# Lyra_Main_Solo.net
KiCad netlist of a schematic drawn in EAGLE
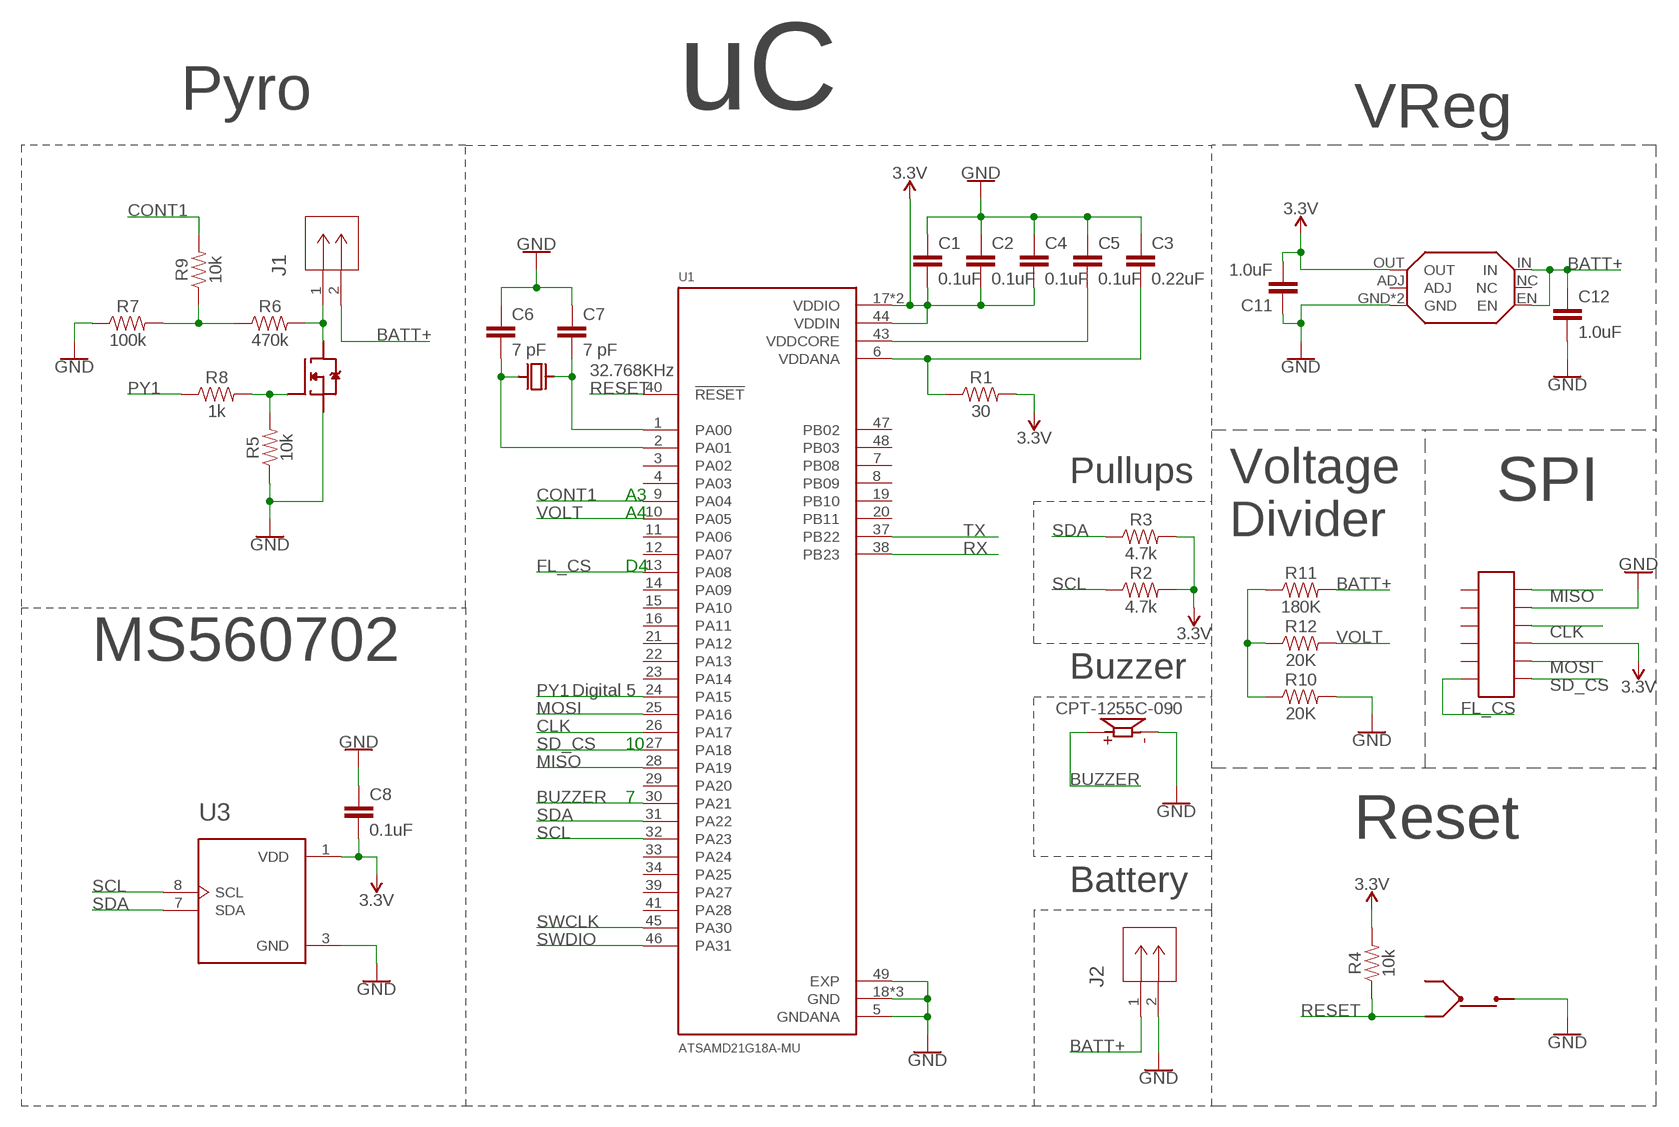
[diagram p0: schematic, sheet 1]

(export (version "E")
  (design (tool "Eeschema 10.0.6"))
  (components
    (comp (ref "C1")
      (value "0.1uF")
      (footprint "eagle-import:0603")
      (libsource (lib "eagle-import") (part "0.1UF-0603-25V-(+80/-20%)"))
    )
    (comp (ref "C2")
      (value "0.1uF")
      (footprint "eagle-import:0603")
      (libsource (lib "eagle-import") (part "0.1UF-0603-25V-(+80/-20%)"))
    )
    (comp (ref "C3")
      (value "0.22uF")
      (footprint "eagle-import:0603")
      (libsource (lib "eagle-import") (part "0.1UF-0603-25V-(+80/-20%)"))
    )
    (comp (ref "C4")
      (value "0.1uF")
      (footprint "eagle-import:0603")
      (libsource (lib "eagle-import") (part "0.1UF-0603-25V-(+80/-20%)"))
    )
    (comp (ref "C5")
      (value "0.1uF")
      (footprint "eagle-import:0603")
      (libsource (lib "eagle-import") (part "0.1UF-0603-25V-(+80/-20%)"))
    )
    (comp (ref "C6")
      (value "7 pF")
      (footprint "eagle-import:0402")
      (libsource (lib "eagle-import") (part "0.1UF-0402-16V-10%"))
    )
    (comp (ref "C7")
      (value "7 pF")
      (footprint "eagle-import:0402")
      (libsource (lib "eagle-import") (part "0.1UF-0402-16V-10%"))
    )
    (comp (ref "C8")
      (value "0.1uF")
      (footprint "eagle-import:0603")
      (libsource (lib "eagle-import") (part "0.1UF-0603-25V-(+80/-20%)"))
    )
    (comp (ref "C11")
      (value "1.0uF")
      (footprint "eagle-import:0402")
      (libsource (lib "eagle-import") (part "1.0UF-0402-16V-10%"))
    )
    (comp (ref "C12")
      (value "1.0uF")
      (footprint "eagle-import:0402")
      (libsource (lib "eagle-import") (part "1.0UF-0402-16V-10%"))
    )
    (comp (ref "J1")
      (value "OSTVN02A150")
      (footprint "eagle-import:CONN_OSTVN02A150_OST")
      (fields (field (name "COPYRIGHT") "Copyright (C) 2018 Accelerated Designs. All rights reserved"))
      (libsource (lib "eagle-import") (part "OSTVN02A150"))
    )
    (comp (ref "J2")
      (value "OSTVN02A150")
      (footprint "eagle-import:CONN_OSTVN02A150_OST")
      (fields (field (name "COPYRIGHT") "Copyright (C) 2018 Accelerated Designs. All rights reserved"))
      (libsource (lib "eagle-import") (part "OSTVN02A150"))
    )
    (comp (ref "LS2")
      (value "CPT-1255C-090")
      (footprint "eagle-import:CUI_CPT-1255C-090")
      (fields (field (name "MF") "CUI Devices"))
      (libsource (lib "eagle-import") (part "CPT-1255C-090"))
    )
    (comp (ref "R1")
      (value "30")
      (footprint "eagle-import:0402")
      (libsource (lib "eagle-import") (part "RESISTOR0402"))
    )
    (comp (ref "R2")
      (value "4.7k")
      (footprint "eagle-import:0603")
      (libsource (lib "eagle-import") (part "4.7KOHM-0603-1/10W-1%"))
    )
    (comp (ref "R3")
      (value "4.7k")
      (footprint "eagle-import:0603")
      (libsource (lib "eagle-import") (part "4.7KOHM-0603-1/10W-1%"))
    )
    (comp (ref "R4")
      (value "10k")
      (footprint "eagle-import:0402")
      (libsource (lib "eagle-import") (part "RESISTOR0402"))
    )
    (comp (ref "R5")
      (value "10k")
      (footprint "eagle-import:0402")
      (libsource (lib "eagle-import") (part "RESISTOR0402"))
    )
    (comp (ref "R6")
      (value "470k")
      (footprint "eagle-import:0402")
      (libsource (lib "eagle-import") (part "RESISTOR0402"))
    )
    (comp (ref "R7")
      (value "100k")
      (footprint "eagle-import:0402")
      (libsource (lib "eagle-import") (part "RESISTOR0402"))
    )
    (comp (ref "R8")
      (value "1k")
      (footprint "eagle-import:0402")
      (libsource (lib "eagle-import") (part "RESISTOR0402"))
    )
    (comp (ref "R9")
      (value "10k")
      (footprint "eagle-import:0402")
      (libsource (lib "eagle-import") (part "RESISTOR0402"))
    )
    (comp (ref "R10")
      (value "20K")
      (footprint "eagle-import:0402")
      (libsource (lib "eagle-import") (part "RESISTOR0402"))
    )
    (comp (ref "R11")
      (value "180K")
      (footprint "eagle-import:0402")
      (libsource (lib "eagle-import") (part "RESISTOR0402"))
    )
    (comp (ref "R12")
      (value "20K")
      (footprint "eagle-import:0402")
      (libsource (lib "eagle-import") (part "RESISTOR0402"))
    )
    (comp (ref "U$1")
      (value "32.768KHz")
      (footprint "eagle-import:FC-135")
      (libsource (lib "eagle-import") (part "FC-135"))
    )
    (comp (ref "U$2")
      (value "IRLHM630PBF")
      (footprint "eagle-import:IRLHM630PBF")
      (libsource (lib "eagle-import") (part "IRLHM630PBF"))
    )
    (comp (ref "U$3")
      (value "NCP718AMT330TBG")
      (footprint "eagle-import:NCP718BMT330TBG")
      (libsource (lib "eagle-import") (part "NCP718AMT330TBG"))
    )
    (comp (ref "U$4")
      (value "BUTTON")
      (footprint "eagle-import:BUTTON")
      (libsource (lib "eagle-import") (part "BUTTON"))
    )
    (comp (ref "U$5")
      (value "12POS_SOCKET")
      (footprint "eagle-import:12POS_SOCKET")
      (libsource (lib "eagle-import") (part "12POS_SOCKET"))
    )
    (comp (ref "U1")
      (value "ATSAMD21G18A-MU")
      (footprint "eagle-import:QFN50P700X700X90-49N")
      (fields (field (name "DIGI-KEY_PART_NUMBER") "ATSAMD21G18A-MUTTR-ND") (field (name "MF") "Microchip"))
      (libsource (lib "eagle-import") (part "ATSAMD21G18A-MU"))
    )
    (comp (ref "U3")
      (value "MS860702BA01-50")
      (footprint "eagle-import:TE_MS860702BA01-50")
      (fields (field (name "MF") "TE Connectivity"))
      (libsource (lib "eagle-import") (part "MS860702BA01-50"))
    )
  )
  (nets
    (net (code "1") (name "/BATT+") (class "Default")
      (node (ref "C12") (pin "1") (pinfunction "1_1") (pintype "passive"))
      (node (ref "J1") (pin "2") (pinfunction "2_2") (pintype "passive"))
      (node (ref "J2") (pin "1") (pinfunction "1_1") (pintype "passive"))
      (node (ref "R11") (pin "2") (pinfunction "2_2") (pintype "passive"))
      (node (ref "U$3") (pin "EN") (pinfunction "EN_EN") (pintype "bidirectional"))
      (node (ref "U$3") (pin "IN") (pinfunction "IN_IN") (pintype "bidirectional"))
    )
    (net (code "2") (name "/BUZZER") (class "Default")
      (node (ref "LS2") (pin "P") (pinfunction "P_P") (pintype "passive"))
      (node (ref "U1") (pin "30") (pinfunction "PA21_30") (pintype "bidirectional"))
    )
    (net (code "3") (name "/CLK") (class "Default")
      (node (ref "U$5") (pin "P$10") (pinfunction "P$10_P$10") (pintype "bidirectional"))
      (node (ref "U1") (pin "26") (pinfunction "PA17_26") (pintype "bidirectional"))
    )
    (net (code "4") (name "/CONT1") (class "Default")
      (node (ref "R9") (pin "2") (pinfunction "2_2") (pintype "passive"))
      (node (ref "U1") (pin "9") (pinfunction "PA04_9") (pintype "bidirectional"))
    )
    (net (code "5") (name "/FL_CS") (class "Default")
      (node (ref "U$5") (pin "P$6") (pinfunction "P$6_P$6") (pintype "bidirectional"))
      (node (ref "U1") (pin "13") (pinfunction "PA08_13") (pintype "bidirectional"))
    )
    (net (code "6") (name "/MISO") (class "Default")
      (node (ref "U$5") (pin "P$12") (pinfunction "P$12_P$12") (pintype "bidirectional"))
      (node (ref "U1") (pin "28") (pinfunction "PA19_28") (pintype "bidirectional"))
    )
    (net (code "7") (name "/MOSI") (class "Default")
      (node (ref "U$5") (pin "P$8") (pinfunction "P$8_P$8") (pintype "bidirectional"))
      (node (ref "U1") (pin "25") (pinfunction "PA16_25") (pintype "bidirectional"))
    )
    (net (code "8") (name "/PY1") (class "Default")
      (node (ref "R8") (pin "1") (pinfunction "1_1") (pintype "passive"))
      (node (ref "U1") (pin "24") (pinfunction "PA15_24") (pintype "bidirectional"))
    )
    (net (code "9") (name "/RESET") (class "Default")
      (node (ref "R4") (pin "1") (pinfunction "1_1") (pintype "passive"))
      (node (ref "U$4") (pin "2") (pinfunction "IN(2)_2") (pintype "bidirectional"))
      (node (ref "U1") (pin "40") (pinfunction "~{RESET}_40") (pintype "input"))
    )
    (net (code "10") (name "/RX") (class "Default")
      (node (ref "U1") (pin "38") (pinfunction "PB23_38") (pintype "bidirectional"))
    )
    (net (code "11") (name "/SCL") (class "Default")
      (node (ref "R2") (pin "1") (pinfunction "1_1") (pintype "passive"))
      (node (ref "U1") (pin "32") (pinfunction "PA23_32") (pintype "bidirectional"))
      (node (ref "U3") (pin "8") (pinfunction "SCL_8") (pintype "input"))
    )
    (net (code "12") (name "/SDA") (class "Default")
      (node (ref "R3") (pin "1") (pinfunction "1_1") (pintype "passive"))
      (node (ref "U1") (pin "31") (pinfunction "PA22_31") (pintype "bidirectional"))
      (node (ref "U3") (pin "7") (pinfunction "SDA_7") (pintype "bidirectional"))
    )
    (net (code "13") (name "/SD_CS") (class "Default")
      (node (ref "U$5") (pin "P$7") (pinfunction "P$7_P$7") (pintype "bidirectional"))
      (node (ref "U1") (pin "27") (pinfunction "PA18_27") (pintype "bidirectional"))
    )
    (net (code "14") (name "/SWCLK") (class "Default")
      (node (ref "U1") (pin "45") (pinfunction "PA30_45") (pintype "bidirectional"))
    )
    (net (code "15") (name "/SWDIO") (class "Default")
      (node (ref "U1") (pin "46") (pinfunction "PA31_46") (pintype "bidirectional"))
    )
    (net (code "16") (name "/TX") (class "Default")
      (node (ref "U1") (pin "37") (pinfunction "PB22_37") (pintype "bidirectional"))
    )
    (net (code "17") (name "/VOLT") (class "Default")
      (node (ref "R12") (pin "2") (pinfunction "2_2") (pintype "passive"))
      (node (ref "U1") (pin "10") (pinfunction "PA05_10") (pintype "bidirectional"))
    )
    (net (code "18") (name "3.3V") (class "Default")
      (node (ref "C1") (pin "2") (pinfunction "2_2") (pintype "passive"))
      (node (ref "C11") (pin "2") (pinfunction "2_2") (pintype "passive"))
      (node (ref "C2") (pin "2") (pinfunction "2_2") (pintype "passive"))
      (node (ref "C4") (pin "2") (pinfunction "2_2") (pintype "passive"))
      (node (ref "C8") (pin "2") (pinfunction "2_2") (pintype "passive"))
      (node (ref "R1") (pin "2") (pinfunction "2_2") (pintype "passive"))
      (node (ref "R2") (pin "2") (pinfunction "2_2") (pintype "passive"))
      (node (ref "R3") (pin "2") (pinfunction "2_2") (pintype "passive"))
      (node (ref "R4") (pin "2") (pinfunction "2_2") (pintype "passive"))
      (node (ref "U$3") (pin "OUT") (pinfunction "OUT_OUT") (pintype "bidirectional"))
      (node (ref "U$5") (pin "P$9") (pinfunction "P$9_P$9") (pintype "bidirectional"))
      (node (ref "U1") (pin "17") (pinfunction "VDDIO_17") (pintype "power_in"))
      (node (ref "U1") (pin "36") (pinfunction "VDDIO_36") (pintype "power_in"))
      (node (ref "U1") (pin "44") (pinfunction "VDDIN_44") (pintype "power_in"))
      (node (ref "U3") (pin "1") (pinfunction "VDD_1") (pintype "power_in"))
    )
    (net (code "19") (name "GND") (class "Default")
      (node (ref "C1") (pin "1") (pinfunction "1_1") (pintype "passive"))
      (node (ref "C11") (pin "1") (pinfunction "1_1") (pintype "passive"))
      (node (ref "C12") (pin "2") (pinfunction "2_2") (pintype "passive"))
      (node (ref "C2") (pin "1") (pinfunction "1_1") (pintype "passive"))
      (node (ref "C3") (pin "1") (pinfunction "1_1") (pintype "passive"))
      (node (ref "C4") (pin "1") (pinfunction "1_1") (pintype "passive"))
      (node (ref "C5") (pin "1") (pinfunction "1_1") (pintype "passive"))
      (node (ref "C6") (pin "1") (pinfunction "1_1") (pintype "passive"))
      (node (ref "C7") (pin "1") (pinfunction "1_1") (pintype "passive"))
      (node (ref "C8") (pin "1") (pinfunction "1_1") (pintype "passive"))
      (node (ref "J2") (pin "2") (pinfunction "2_2") (pintype "passive"))
      (node (ref "LS2") (pin "N") (pinfunction "N_N") (pintype "passive"))
      (node (ref "R10") (pin "2") (pinfunction "2_2") (pintype "passive"))
      (node (ref "R5") (pin "1") (pinfunction "1_1") (pintype "passive"))
      (node (ref "R7") (pin "1") (pinfunction "1_1") (pintype "passive"))
      (node (ref "U$2") (pin "P$2") (pinfunction "P$1_P$2") (pintype "bidirectional"))
      (node (ref "U$2") (pin "P$3") (pinfunction "P$1_P$3") (pintype "bidirectional"))
      (node (ref "U$2") (pin "P$4") (pinfunction "P$1_P$4") (pintype "bidirectional"))
      (node (ref "U$3") (pin "GND") (pinfunction "GND_GND") (pintype "bidirectional"))
      (node (ref "U$3") (pin "P$7") (pinfunction "GND_P$7") (pintype "bidirectional"))
      (node (ref "U$4") (pin "4") (pinfunction "OUT_4") (pintype "bidirectional"))
      (node (ref "U$5") (pin "P$11") (pinfunction "P$11_P$11") (pintype "bidirectional"))
      (node (ref "U1") (pin "18") (pinfunction "GND_18") (pintype "power_in"))
      (node (ref "U1") (pin "35") (pinfunction "GND_35") (pintype "power_in"))
      (node (ref "U1") (pin "42") (pinfunction "GND_42") (pintype "power_in"))
      (node (ref "U1") (pin "49") (pinfunction "EXP_49") (pintype "power_in"))
      (node (ref "U1") (pin "5") (pinfunction "GNDANA_5") (pintype "power_in"))
      (node (ref "U3") (pin "3") (pinfunction "GND_3") (pintype "power_in"))
    )
    (net (code "20") (name "Net-(J1-Pad1)") (class "Default")
      (node (ref "J1") (pin "1") (pinfunction "1_1") (pintype "passive"))
      (node (ref "R6") (pin "2") (pinfunction "2_2") (pintype "passive"))
      (node (ref "U$2") (pin "P$5") (pinfunction "P$3_P$5") (pintype "bidirectional"))
      (node (ref "U$2") (pin "P$6") (pinfunction "P$3_P$6") (pintype "bidirectional"))
      (node (ref "U$2") (pin "P$7") (pinfunction "P$3_P$7") (pintype "bidirectional"))
      (node (ref "U$2") (pin "P$8") (pinfunction "P$3_P$8") (pintype "bidirectional"))
      (node (ref "U$2") (pin "P$9") (pinfunction "P$3_P$9") (pintype "bidirectional"))
    )
    (net (code "21") (name "Net-(R6-Pad1)") (class "Default")
      (node (ref "R6") (pin "1") (pinfunction "1_1") (pintype "passive"))
      (node (ref "R7") (pin "2") (pinfunction "2_2") (pintype "passive"))
      (node (ref "R9") (pin "1") (pinfunction "1_1") (pintype "passive"))
    )
    (net (code "22") (name "Net-(R10-Pad1)") (class "Default")
      (node (ref "R10") (pin "1") (pinfunction "1_1") (pintype "passive"))
      (node (ref "R11") (pin "1") (pinfunction "1_1") (pintype "passive"))
      (node (ref "R12") (pin "1") (pinfunction "1_1") (pintype "passive"))
    )
    (net (code "23") (name "Net-(U$2-P$2)") (class "Default")
      (node (ref "R5") (pin "2") (pinfunction "2_2") (pintype "passive"))
      (node (ref "R8") (pin "2") (pinfunction "2_2") (pintype "passive"))
      (node (ref "U$2") (pin "P$1") (pinfunction "P$2_P$1") (pintype "bidirectional"))
    )
    (net (code "24") (name "Net-(U1-PA00)") (class "Default")
      (node (ref "C7") (pin "2") (pinfunction "2_2") (pintype "passive"))
      (node (ref "U$1") (pin "P$2") (pinfunction "P$2_P$2") (pintype "bidirectional"))
      (node (ref "U1") (pin "1") (pinfunction "PA00_1") (pintype "bidirectional"))
    )
    (net (code "25") (name "Net-(U1-PA01)") (class "Default")
      (node (ref "C6") (pin "2") (pinfunction "2_2") (pintype "passive"))
      (node (ref "U$1") (pin "P$1") (pinfunction "P$1_P$1") (pintype "bidirectional"))
      (node (ref "U1") (pin "2") (pinfunction "PA01_2") (pintype "bidirectional"))
    )
    (net (code "26") (name "Net-(U1-VDDANA)") (class "Default")
      (node (ref "C3") (pin "2") (pinfunction "2_2") (pintype "passive"))
      (node (ref "R1") (pin "1") (pinfunction "1_1") (pintype "passive"))
      (node (ref "U1") (pin "6") (pinfunction "VDDANA_6") (pintype "power_in"))
    )
    (net (code "27") (name "Net-(U1-VDDCORE)") (class "Default")
      (node (ref "C5") (pin "2") (pinfunction "2_2") (pintype "passive"))
      (node (ref "U1") (pin "43") (pinfunction "VDDCORE_43") (pintype "power_in"))
    )
    (net (code "28") (name "unconnected-(U$3-PadADJ)") (class "Default")
      (node (ref "U$3") (pin "ADJ") (pinfunction "ADJ_ADJ") (pintype "bidirectional"))
    )
    (net (code "29") (name "unconnected-(U$3-PadNC)") (class "Default")
      (node (ref "U$3") (pin "NC") (pinfunction "NC_NC") (pintype "bidirectional"))
    )
    (net (code "30") (name "unconnected-(U$4-IN-Pad1)") (class "Default")
      (node (ref "U$4") (pin "1") (pinfunction "IN_1") (pintype "bidirectional"))
    )
    (net (code "31") (name "unconnected-(U$5-PadP$1)") (class "Default")
      (node (ref "U$5") (pin "P$1") (pinfunction "P$1_P$1") (pintype "bidirectional"))
    )
    (net (code "32") (name "unconnected-(U$5-PadP$2)") (class "Default")
      (node (ref "U$5") (pin "P$2") (pinfunction "P$2_P$2") (pintype "bidirectional"))
    )
    (net (code "33") (name "unconnected-(U$5-PadP$3)") (class "Default")
      (node (ref "U$5") (pin "P$3") (pinfunction "P$3_P$3") (pintype "bidirectional"))
    )
    (net (code "34") (name "unconnected-(U$5-PadP$4)") (class "Default")
      (node (ref "U$5") (pin "P$4") (pinfunction "P$4_P$4") (pintype "bidirectional"))
    )
    (net (code "35") (name "unconnected-(U$5-PadP$5)") (class "Default")
      (node (ref "U$5") (pin "P$5") (pinfunction "P$5_P$5") (pintype "bidirectional"))
    )
    (net (code "36") (name "unconnected-(U1-PA02-Pad3)") (class "Default")
      (node (ref "U1") (pin "3") (pinfunction "PA02_3") (pintype "bidirectional"))
    )
    (net (code "37") (name "unconnected-(U1-PA03-Pad4)") (class "Default")
      (node (ref "U1") (pin "4") (pinfunction "PA03_4") (pintype "bidirectional"))
    )
    (net (code "38") (name "unconnected-(U1-PA06-Pad11)") (class "Default")
      (node (ref "U1") (pin "11") (pinfunction "PA06_11") (pintype "bidirectional"))
    )
    (net (code "39") (name "unconnected-(U1-PA07-Pad12)") (class "Default")
      (node (ref "U1") (pin "12") (pinfunction "PA07_12") (pintype "bidirectional"))
    )
    (net (code "40") (name "unconnected-(U1-PA09-Pad14)") (class "Default")
      (node (ref "U1") (pin "14") (pinfunction "PA09_14") (pintype "bidirectional"))
    )
    (net (code "41") (name "unconnected-(U1-PA10-Pad15)") (class "Default")
      (node (ref "U1") (pin "15") (pinfunction "PA10_15") (pintype "bidirectional"))
    )
    (net (code "42") (name "unconnected-(U1-PA11-Pad16)") (class "Default")
      (node (ref "U1") (pin "16") (pinfunction "PA11_16") (pintype "bidirectional"))
    )
    (net (code "43") (name "unconnected-(U1-PA12-Pad21)") (class "Default")
      (node (ref "U1") (pin "21") (pinfunction "PA12_21") (pintype "bidirectional"))
    )
    (net (code "44") (name "unconnected-(U1-PA13-Pad22)") (class "Default")
      (node (ref "U1") (pin "22") (pinfunction "PA13_22") (pintype "bidirectional"))
    )
    (net (code "45") (name "unconnected-(U1-PA14-Pad23)") (class "Default")
      (node (ref "U1") (pin "23") (pinfunction "PA14_23") (pintype "bidirectional"))
    )
    (net (code "46") (name "unconnected-(U1-PA20-Pad29)") (class "Default")
      (node (ref "U1") (pin "29") (pinfunction "PA20_29") (pintype "bidirectional"))
    )
    (net (code "47") (name "unconnected-(U1-PA24-Pad33)") (class "Default")
      (node (ref "U1") (pin "33") (pinfunction "PA24_33") (pintype "bidirectional"))
    )
    (net (code "48") (name "unconnected-(U1-PA25-Pad34)") (class "Default")
      (node (ref "U1") (pin "34") (pinfunction "PA25_34") (pintype "bidirectional"))
    )
    (net (code "49") (name "unconnected-(U1-PA27-Pad39)") (class "Default")
      (node (ref "U1") (pin "39") (pinfunction "PA27_39") (pintype "bidirectional"))
    )
    (net (code "50") (name "unconnected-(U1-PA28-Pad41)") (class "Default")
      (node (ref "U1") (pin "41") (pinfunction "PA28_41") (pintype "bidirectional"))
    )
    (net (code "51") (name "unconnected-(U1-PB02-Pad47)") (class "Default")
      (node (ref "U1") (pin "47") (pinfunction "PB02_47") (pintype "bidirectional"))
    )
    (net (code "52") (name "unconnected-(U1-PB03-Pad48)") (class "Default")
      (node (ref "U1") (pin "48") (pinfunction "PB03_48") (pintype "bidirectional"))
    )
    (net (code "53") (name "unconnected-(U1-PB08-Pad7)") (class "Default")
      (node (ref "U1") (pin "7") (pinfunction "PB08_7") (pintype "bidirectional"))
    )
    (net (code "54") (name "unconnected-(U1-PB09-Pad8)") (class "Default")
      (node (ref "U1") (pin "8") (pinfunction "PB09_8") (pintype "bidirectional"))
    )
    (net (code "55") (name "unconnected-(U1-PB10-Pad19)") (class "Default")
      (node (ref "U1") (pin "19") (pinfunction "PB10_19") (pintype "bidirectional"))
    )
    (net (code "56") (name "unconnected-(U1-PB11-Pad20)") (class "Default")
      (node (ref "U1") (pin "20") (pinfunction "PB11_20") (pintype "bidirectional"))
    )
  )
)
